# Esquema20_-_Final.net
KiCad netlist of a schematic drawn in EAGLE
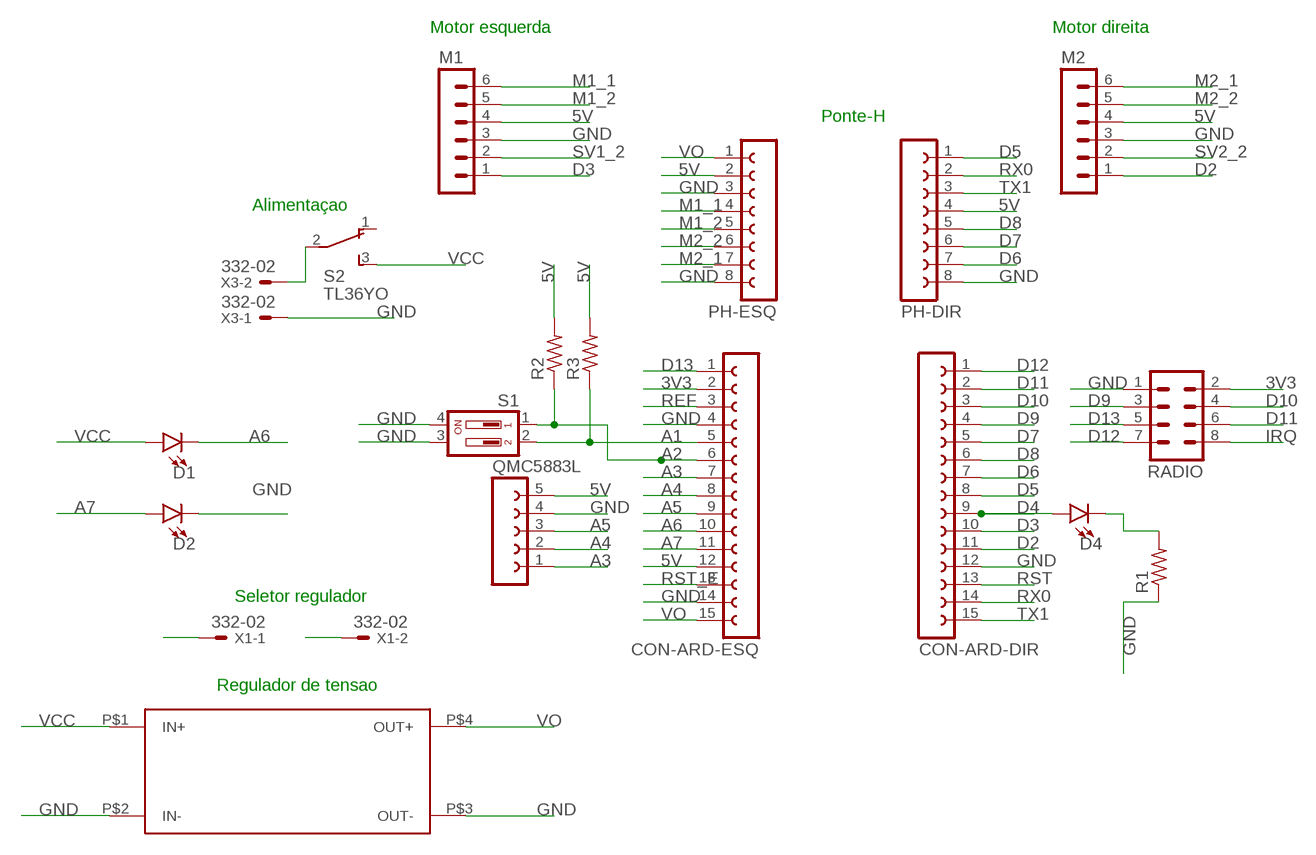
[diagram p0: schematic, sheet 1]

(export (version "E")
  (design (tool "Eeschema 10.0.6"))
  (components
    (comp (ref "CON-ARD-DIR")
      (value "FE15-1")
      (footprint "eagle-import:FE15")
      (libsource (lib "eagle-import") (part "FE15-1"))
    )
    (comp (ref "CON-ARD-ESQ")
      (value "FE15-1")
      (footprint "eagle-import:FE15")
      (fields (field (name "SPICEPREFIX") "X"))
      (libsource (lib "eagle-import") (part "FE15-1"))
    )
    (comp (ref "D1")
      (value "LED-3MM-NO_SILK")
      (footprint "eagle-import:LED_3MM-NS")
      (libsource (lib "eagle-import") (part "LED-3MM-NO_SILK"))
    )
    (comp (ref "D2")
      (value "LED-3MM-NO_SILK")
      (footprint "eagle-import:LED_3MM-NS")
      (libsource (lib "eagle-import") (part "LED-3MM-NO_SILK"))
    )
    (comp (ref "D4")
      (value "LED-3MM-NO_SILK")
      (footprint "eagle-import:LED_3MM-NS")
      (libsource (lib "eagle-import") (part "LED-3MM-NO_SILK"))
    )
    (comp (ref "M1")
      (value "MA06-1")
      (footprint "eagle-import:MA06-1")
      (libsource (lib "eagle-import") (part "MA06-1"))
    )
    (comp (ref "M2")
      (value "MA06-1")
      (footprint "eagle-import:MA06-1")
      (libsource (lib "eagle-import") (part "MA06-1"))
    )
    (comp (ref "PH-DIR")
      (value "FE08-1")
      (footprint "eagle-import:FE08")
      (libsource (lib "eagle-import") (part "FE08-1"))
    )
    (comp (ref "PH-ESQ")
      (value "FE08-1")
      (footprint "eagle-import:FE08")
      (libsource (lib "eagle-import") (part "FE08-1"))
    )
    (comp (ref "QMC5883L")
      (value "FE05W")
      (footprint "eagle-import:FE05W")
      (libsource (lib "eagle-import") (part "FE05W"))
    )
    (comp (ref "R1")
      (value "R-US_0207/12")
      (footprint "eagle-import:0207_12")
      (libsource (lib "eagle-import") (part "R-US_0207/12"))
    )
    (comp (ref "R2")
      (value "R-US_0207/12")
      (footprint "eagle-import:0207_12")
      (libsource (lib "eagle-import") (part "R-US_0207/12"))
    )
    (comp (ref "R3")
      (value "R-US_0207/12")
      (footprint "eagle-import:0207_12")
      (libsource (lib "eagle-import") (part "R-US_0207/12"))
    )
    (comp (ref "RADIO")
      (value "MA04-2")
      (footprint "eagle-import:MA04-2")
      (libsource (lib "eagle-import") (part "MA04-2"))
    )
    (comp (ref "S1")
      (value "DA02")
      (footprint "eagle-import:DA-02")
      (libsource (lib "eagle-import") (part "DA02"))
    )
    (comp (ref "S2")
      (value "TL36YO")
      (footprint "eagle-import:TL3XYO")
      (libsource (lib "eagle-import") (part "TL36YO"))
    )
    (comp (ref "U$1")
      (value "REGULADOR")
      (footprint "eagle-import:REGULADOR-FP")
      (libsource (lib "eagle-import") (part "REGULADOR"))
    )
    (comp (ref "X1")
      (value "332-02")
      (footprint "eagle-import:332-02")
      (libsource (lib "eagle-import") (part "332-02"))
    )
    (comp (ref "X3")
      (value "332-02")
      (footprint "eagle-import:332-02")
      (libsource (lib "eagle-import") (part "332-02"))
    )
  )
  (nets
    (net (code "1") (name "/3V3") (class "Default")
      (node (ref "CON-ARD-ESQ") (pin "2") (pinfunction "2_2") (pintype "passive"))
      (node (ref "RADIO") (pin "2") (pinfunction "2_2") (pintype "passive"))
    )
    (net (code "2") (name "/5V") (class "Default")
      (node (ref "CON-ARD-ESQ") (pin "12") (pinfunction "12_12") (pintype "passive"))
      (node (ref "M1") (pin "4") (pinfunction "4_4") (pintype "passive"))
      (node (ref "M2") (pin "4") (pinfunction "4_4") (pintype "passive"))
      (node (ref "PH-DIR") (pin "4") (pinfunction "4_4") (pintype "passive"))
      (node (ref "PH-ESQ") (pin "2") (pinfunction "2_2") (pintype "passive"))
      (node (ref "QMC5883L") (pin "5") (pinfunction "5_5") (pintype "passive"))
      (node (ref "R2") (pin "2") (pinfunction "2_2") (pintype "passive"))
      (node (ref "R3") (pin "2") (pinfunction "2_2") (pintype "passive"))
    )
    (net (code "3") (name "/A1") (class "Default")
      (node (ref "CON-ARD-ESQ") (pin "5") (pinfunction "5_5") (pintype "passive"))
      (node (ref "R3") (pin "1") (pinfunction "1_1") (pintype "passive"))
      (node (ref "S1") (pin "2") (pinfunction "2_2") (pintype "passive"))
    )
    (net (code "4") (name "/A2") (class "Default")
      (node (ref "CON-ARD-ESQ") (pin "6") (pinfunction "6_6") (pintype "passive"))
      (node (ref "R2") (pin "1") (pinfunction "1_1") (pintype "passive"))
      (node (ref "S1") (pin "1") (pinfunction "1_1") (pintype "passive"))
    )
    (net (code "5") (name "/A3") (class "Default")
      (node (ref "CON-ARD-ESQ") (pin "7") (pinfunction "7_7") (pintype "passive"))
      (node (ref "QMC5883L") (pin "1") (pinfunction "1_1") (pintype "passive"))
    )
    (net (code "6") (name "/A4") (class "Default")
      (node (ref "CON-ARD-ESQ") (pin "8") (pinfunction "8_8") (pintype "passive"))
      (node (ref "QMC5883L") (pin "2") (pinfunction "2_2") (pintype "passive"))
    )
    (net (code "7") (name "/A5") (class "Default")
      (node (ref "CON-ARD-ESQ") (pin "9") (pinfunction "9_9") (pintype "passive"))
      (node (ref "QMC5883L") (pin "3") (pinfunction "3_3") (pintype "passive"))
    )
    (net (code "8") (name "/A6") (class "Default")
      (node (ref "CON-ARD-ESQ") (pin "10") (pinfunction "10_10") (pintype "passive"))
      (node (ref "D1") (pin "K") (pinfunction "C_K") (pintype "passive"))
    )
    (net (code "9") (name "/A7") (class "Default")
      (node (ref "CON-ARD-ESQ") (pin "11") (pinfunction "11_11") (pintype "passive"))
      (node (ref "D2") (pin "A") (pinfunction "A_A") (pintype "passive"))
    )
    (net (code "10") (name "/D2") (class "Default")
      (node (ref "CON-ARD-DIR") (pin "11") (pinfunction "11_11") (pintype "passive"))
      (node (ref "M2") (pin "1") (pinfunction "1_1") (pintype "passive"))
    )
    (net (code "11") (name "/D3") (class "Default")
      (node (ref "CON-ARD-DIR") (pin "10") (pinfunction "10_10") (pintype "passive"))
      (node (ref "M1") (pin "1") (pinfunction "1_1") (pintype "passive"))
    )
    (net (code "12") (name "/D4") (class "Default")
      (node (ref "CON-ARD-DIR") (pin "9") (pinfunction "9_9") (pintype "passive"))
      (node (ref "D4") (pin "A") (pinfunction "A_A") (pintype "passive"))
    )
    (net (code "13") (name "/D5") (class "Default")
      (node (ref "CON-ARD-DIR") (pin "8") (pinfunction "8_8") (pintype "passive"))
      (node (ref "PH-DIR") (pin "1") (pinfunction "1_1") (pintype "passive"))
    )
    (net (code "14") (name "/D6") (class "Default")
      (node (ref "CON-ARD-DIR") (pin "7") (pinfunction "7_7") (pintype "passive"))
      (node (ref "PH-DIR") (pin "7") (pinfunction "7_7") (pintype "passive"))
    )
    (net (code "15") (name "/D7") (class "Default")
      (node (ref "CON-ARD-DIR") (pin "5") (pinfunction "5_5") (pintype "passive"))
      (node (ref "PH-DIR") (pin "6") (pinfunction "6_6") (pintype "passive"))
    )
    (net (code "16") (name "/D8") (class "Default")
      (node (ref "CON-ARD-DIR") (pin "6") (pinfunction "6_6") (pintype "passive"))
      (node (ref "PH-DIR") (pin "5") (pinfunction "5_5") (pintype "passive"))
    )
    (net (code "17") (name "/D9") (class "Default")
      (node (ref "CON-ARD-DIR") (pin "4") (pinfunction "4_4") (pintype "passive"))
      (node (ref "RADIO") (pin "3") (pinfunction "3_3") (pintype "passive"))
    )
    (net (code "18") (name "/D10") (class "Default")
      (node (ref "CON-ARD-DIR") (pin "3") (pinfunction "3_3") (pintype "passive"))
      (node (ref "RADIO") (pin "4") (pinfunction "4_4") (pintype "passive"))
    )
    (net (code "19") (name "/D11") (class "Default")
      (node (ref "CON-ARD-DIR") (pin "2") (pinfunction "2_2") (pintype "passive"))
      (node (ref "RADIO") (pin "6") (pinfunction "6_6") (pintype "passive"))
    )
    (net (code "20") (name "/D12") (class "Default")
      (node (ref "CON-ARD-DIR") (pin "1") (pinfunction "1_1") (pintype "passive"))
      (node (ref "RADIO") (pin "7") (pinfunction "7_7") (pintype "passive"))
    )
    (net (code "21") (name "/D13") (class "Default")
      (node (ref "CON-ARD-ESQ") (pin "1") (pinfunction "1_1") (pintype "passive"))
      (node (ref "RADIO") (pin "5") (pinfunction "5_5") (pintype "passive"))
    )
    (net (code "22") (name "/GND") (class "Default")
      (node (ref "CON-ARD-DIR") (pin "12") (pinfunction "12_12") (pintype "passive"))
      (node (ref "CON-ARD-ESQ") (pin "14") (pinfunction "14_14") (pintype "passive"))
      (node (ref "CON-ARD-ESQ") (pin "4") (pinfunction "4_4") (pintype "passive"))
      (node (ref "D2") (pin "K") (pinfunction "C_K") (pintype "passive"))
      (node (ref "M1") (pin "3") (pinfunction "3_3") (pintype "passive"))
      (node (ref "M2") (pin "3") (pinfunction "3_3") (pintype "passive"))
      (node (ref "PH-DIR") (pin "8") (pinfunction "8_8") (pintype "passive"))
      (node (ref "PH-ESQ") (pin "3") (pinfunction "3_3") (pintype "passive"))
      (node (ref "PH-ESQ") (pin "8") (pinfunction "8_8") (pintype "passive"))
      (node (ref "QMC5883L") (pin "4") (pinfunction "4_4") (pintype "passive"))
      (node (ref "R1") (pin "1") (pinfunction "1_1") (pintype "passive"))
      (node (ref "RADIO") (pin "1") (pinfunction "1_1") (pintype "passive"))
      (node (ref "S1") (pin "3") (pinfunction "3_3") (pintype "passive"))
      (node (ref "S1") (pin "4") (pinfunction "4_4") (pintype "passive"))
      (node (ref "U$1") (pin "P$2") (pinfunction "IN-_P$2") (pintype "bidirectional"))
      (node (ref "U$1") (pin "P$3") (pinfunction "OUT-_P$3") (pintype "bidirectional"))
      (node (ref "X3") (pin "1") (pinfunction "S_1") (pintype "passive"))
    )
    (net (code "23") (name "/IRQ") (class "Default")
      (node (ref "RADIO") (pin "8") (pinfunction "8_8") (pintype "passive"))
    )
    (net (code "24") (name "/M1_1") (class "Default")
      (node (ref "M1") (pin "6") (pinfunction "6_6") (pintype "passive"))
      (node (ref "PH-ESQ") (pin "4") (pinfunction "4_4") (pintype "passive"))
    )
    (net (code "25") (name "/M1_2") (class "Default")
      (node (ref "M1") (pin "5") (pinfunction "5_5") (pintype "passive"))
      (node (ref "PH-ESQ") (pin "5") (pinfunction "5_5") (pintype "passive"))
    )
    (net (code "26") (name "/M2_1") (class "Default")
      (node (ref "M2") (pin "6") (pinfunction "6_6") (pintype "passive"))
      (node (ref "PH-ESQ") (pin "7") (pinfunction "7_7") (pintype "passive"))
    )
    (net (code "27") (name "/M2_2") (class "Default")
      (node (ref "M2") (pin "5") (pinfunction "5_5") (pintype "passive"))
      (node (ref "PH-ESQ") (pin "6") (pinfunction "6_6") (pintype "passive"))
    )
    (net (code "28") (name "/REF") (class "Default")
      (node (ref "CON-ARD-ESQ") (pin "3") (pinfunction "3_3") (pintype "passive"))
    )
    (net (code "29") (name "/RST") (class "Default")
      (node (ref "CON-ARD-DIR") (pin "13") (pinfunction "13_13") (pintype "passive"))
    )
    (net (code "30") (name "/RST_E") (class "Default")
      (node (ref "CON-ARD-ESQ") (pin "13") (pinfunction "13_13") (pintype "passive"))
    )
    (net (code "31") (name "/RX0") (class "Default")
      (node (ref "CON-ARD-DIR") (pin "14") (pinfunction "14_14") (pintype "passive"))
      (node (ref "PH-DIR") (pin "2") (pinfunction "2_2") (pintype "passive"))
    )
    (net (code "32") (name "/SV1_2") (class "Default")
      (node (ref "M1") (pin "2") (pinfunction "2_2") (pintype "passive"))
    )
    (net (code "33") (name "/SV2_2") (class "Default")
      (node (ref "M2") (pin "2") (pinfunction "2_2") (pintype "passive"))
    )
    (net (code "34") (name "/TX1") (class "Default")
      (node (ref "CON-ARD-DIR") (pin "15") (pinfunction "15_15") (pintype "passive"))
      (node (ref "PH-DIR") (pin "3") (pinfunction "3_3") (pintype "passive"))
    )
    (net (code "35") (name "/VCC") (class "Default")
      (node (ref "D1") (pin "A") (pinfunction "A_A") (pintype "passive"))
      (node (ref "S2") (pin "3") (pinfunction "S_3") (pintype "passive"))
      (node (ref "U$1") (pin "P$1") (pinfunction "IN+_P$1") (pintype "bidirectional"))
      (node (ref "X1") (pin "1") (pinfunction "S_1") (pintype "passive"))
    )
    (net (code "36") (name "/VO") (class "Default")
      (node (ref "CON-ARD-ESQ") (pin "15") (pinfunction "15_15") (pintype "passive"))
      (node (ref "PH-ESQ") (pin "1") (pinfunction "1_1") (pintype "passive"))
      (node (ref "U$1") (pin "P$4") (pinfunction "OUT+_P$4") (pintype "bidirectional"))
      (node (ref "X1") (pin "2") (pinfunction "S_2") (pintype "passive"))
    )
    (net (code "37") (name "Net-(D4-C)") (class "Default")
      (node (ref "D4") (pin "K") (pinfunction "C_K") (pintype "passive"))
      (node (ref "R1") (pin "2") (pinfunction "2_2") (pintype "passive"))
    )
    (net (code "38") (name "Net-(S2-P)") (class "Default")
      (node (ref "S2") (pin "2") (pinfunction "P_2") (pintype "passive"))
      (node (ref "X3") (pin "2") (pinfunction "S_2") (pintype "passive"))
    )
    (net (code "39") (name "unconnected-(S2-O-Pad1)") (class "Default")
      (node (ref "S2") (pin "1") (pinfunction "O_1") (pintype "passive"))
    )
  )
)
